# 04-AUDIO_TEST.net
KiCad netlist of a schematic drawn in Altium Designer
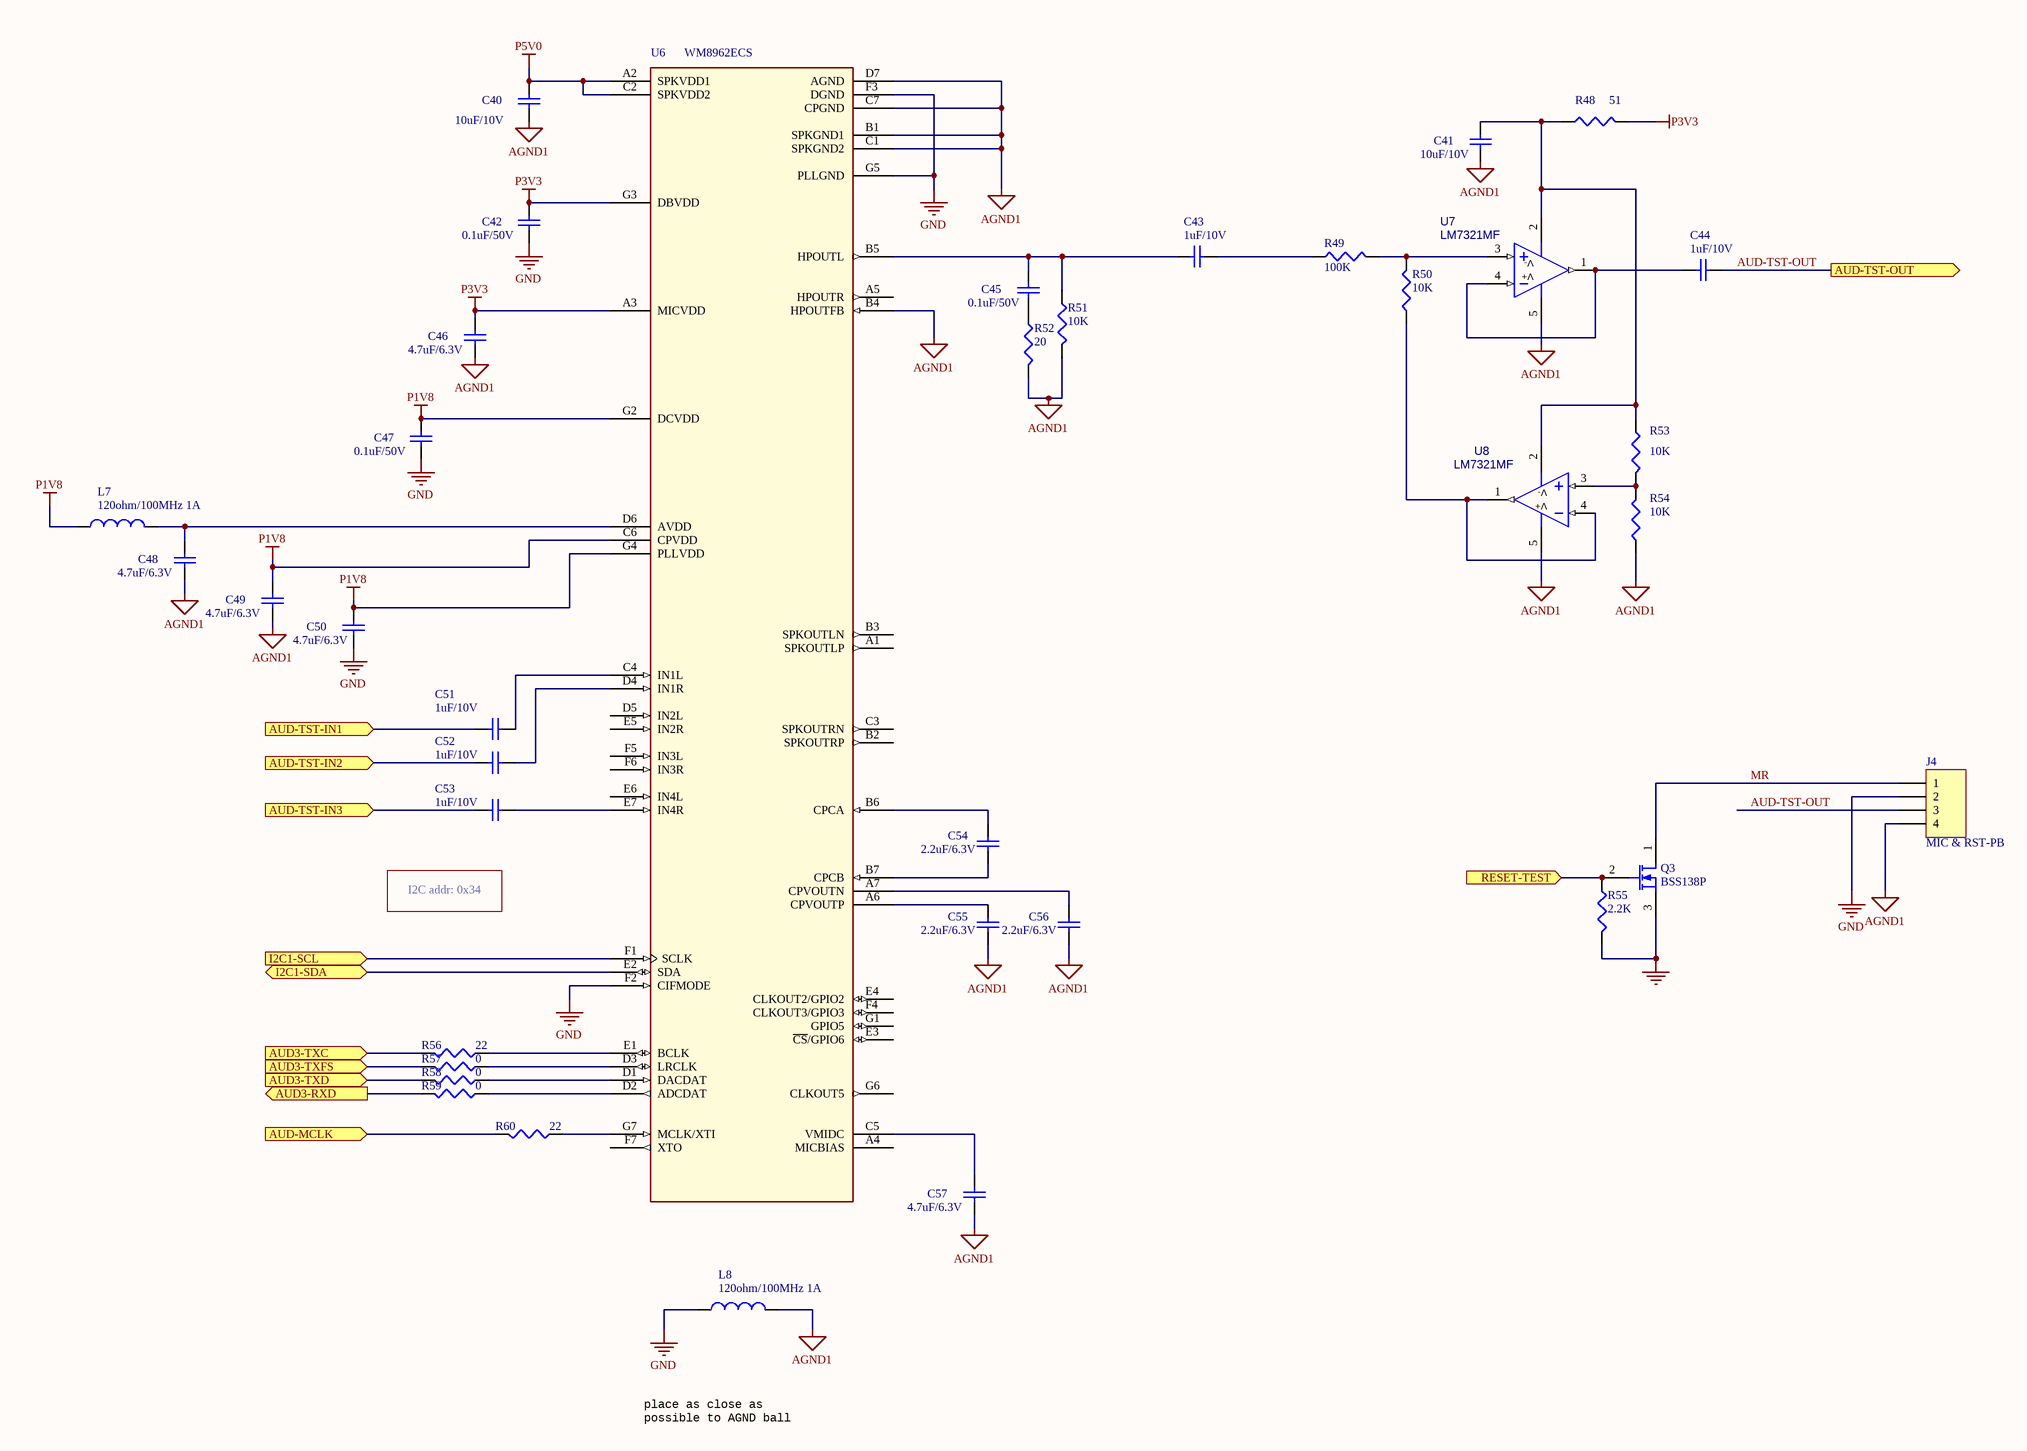
[diagram p0: 04-AUDIO_TEST.SchDoc]

(export (version "E")
  (design (tool "Eeschema 10.0.6"))
  (components
    (comp (ref "C40")
      (value "10uF/10V")
      (footprint "0805")
      (description "Capacitor")
      (fields (field (name "PUBLISHER") "Altium Limited"))
      (libsource (lib "Miscellaneous Devices") (part "Cap"))
    )
    (comp (ref "C41")
      (value "10uF/10V")
      (footprint "0805")
      (description "Capacitor")
      (fields (field (name "PUBLISHER") "Altium Limited"))
      (libsource (lib "Miscellaneous Devices") (part "Cap"))
    )
    (comp (ref "C42")
      (value "0.1uF/50V")
      (footprint "0402")
      (description "Capacitor")
      (fields (field (name "PUBLISHER") "Altium Limited"))
      (libsource (lib "Miscellaneous Devices") (part "Cap"))
    )
    (comp (ref "C43")
      (value "1uF/10V")
      (footprint "0402")
      (description "Capacitor")
      (fields (field (name "PUBLISHER") "Altium Limited"))
      (libsource (lib "Miscellaneous Devices") (part "Cap"))
    )
    (comp (ref "C44")
      (value "1uF/10V")
      (footprint "0402")
      (description "Capacitor")
      (fields (field (name "PUBLISHER") "Altium Limited"))
      (libsource (lib "Miscellaneous Devices") (part "Cap"))
    )
    (comp (ref "C45")
      (value "0.1uF/50V")
      (footprint "0402")
      (description "Capacitor")
      (fields (field (name "PUBLISHER") "Altium Limited"))
      (libsource (lib "Miscellaneous Devices") (part "Cap"))
    )
    (comp (ref "C46")
      (value "4.7uF/6.3V")
      (footprint "0603")
      (description "Capacitor")
      (fields (field (name "PUBLISHER") "Altium Limited"))
      (libsource (lib "Miscellaneous Devices") (part "Cap"))
    )
    (comp (ref "C47")
      (value "0.1uF/50V")
      (footprint "0402")
      (description "Capacitor")
      (fields (field (name "PUBLISHER") "Altium Limited"))
      (libsource (lib "Miscellaneous Devices") (part "Cap"))
    )
    (comp (ref "C48")
      (value "4.7uF/6.3V")
      (footprint "0603")
      (description "Capacitor")
      (fields (field (name "PUBLISHER") "Altium Limited"))
      (libsource (lib "Miscellaneous Devices") (part "Cap"))
    )
    (comp (ref "C49")
      (value "4.7uF/6.3V")
      (footprint "0603")
      (description "Capacitor")
      (fields (field (name "PUBLISHER") "Altium Limited"))
      (libsource (lib "Miscellaneous Devices") (part "Cap"))
    )
    (comp (ref "C50")
      (value "4.7uF/6.3V")
      (footprint "0603")
      (description "Capacitor")
      (fields (field (name "PUBLISHER") "Altium Limited"))
      (libsource (lib "Miscellaneous Devices") (part "Cap"))
    )
    (comp (ref "C51")
      (value "1uF/10V")
      (footprint "0402")
      (description "Capacitor")
      (fields (field (name "PUBLISHER") "Altium Limited"))
      (libsource (lib "Miscellaneous Devices") (part "Cap"))
    )
    (comp (ref "C52")
      (value "1uF/10V")
      (footprint "0402")
      (description "Capacitor")
      (fields (field (name "PUBLISHER") "Altium Limited"))
      (libsource (lib "Miscellaneous Devices") (part "Cap"))
    )
    (comp (ref "C53")
      (value "1uF/10V")
      (footprint "0402")
      (description "Capacitor")
      (fields (field (name "PUBLISHER") "Altium Limited"))
      (libsource (lib "Miscellaneous Devices") (part "Cap"))
    )
    (comp (ref "C54")
      (value "2.2uF/6.3V")
      (footprint "0402")
      (description "Capacitor")
      (fields (field (name "PUBLISHER") "Altium Limited"))
      (libsource (lib "Miscellaneous Devices") (part "Cap"))
    )
    (comp (ref "C55")
      (value "2.2uF/6.3V")
      (footprint "0402")
      (description "Capacitor")
      (fields (field (name "PUBLISHER") "Altium Limited"))
      (libsource (lib "Miscellaneous Devices") (part "Cap"))
    )
    (comp (ref "C56")
      (value "2.2uF/6.3V")
      (footprint "0402")
      (description "Capacitor")
      (fields (field (name "PUBLISHER") "Altium Limited"))
      (libsource (lib "Miscellaneous Devices") (part "Cap"))
    )
    (comp (ref "C57")
      (value "4.7uF/6.3V")
      (footprint "0603")
      (description "Capacitor")
      (fields (field (name "PUBLISHER") "Altium Limited"))
      (libsource (lib "Miscellaneous Devices") (part "Cap"))
    )
    (comp (ref "J4")
      (value "MIC & RST-PB")
      (footprint "FPC1.0-DR-SMD-4P-F2.0")
      (description "Header, 4-Pin")
      (fields (field (name "PUBLISHER") "Altium Limited"))
      (libsource (lib "Miscellaneous Connectors") (part "Header 4"))
    )
    (comp (ref "L7")
      (value "120ohm/100MHz 1A")
      (footprint "0603")
      (description "Inductor")
      (fields (field (name "PUBLISHER") "Altium Limited"))
      (libsource (lib "Miscellaneous Devices") (part "Inductor"))
    )
    (comp (ref "L8")
      (value "120ohm/100MHz 1A")
      (footprint "0603")
      (description "Inductor")
      (fields (field (name "PUBLISHER") "Altium Limited"))
      (libsource (lib "Miscellaneous Devices") (part "Inductor"))
    )
    (comp (ref "Q3")
      (value "BSS138P")
      (footprint "NPN")
      (description "N-Channel MOSFET")
      (fields (field (name "PUBLISHER") "Altium Limited"))
      (libsource (lib "Miscellaneous Devices") (part "MOSFET-N"))
    )
    (comp (ref "R48") (value "51") (footprint "0402") (libsource (lib "*") (part "CR16-1003FM")))
    (comp (ref "R49") (value "100K") (footprint "0402") (libsource (lib "*") (part "CR16-1003FM")))
    (comp (ref "R50") (value "10K") (footprint "0402") (libsource (lib "*") (part "CR16-1003FM")))
    (comp (ref "R51") (value "10K") (footprint "0402") (libsource (lib "*") (part "CR16-1003FM")))
    (comp (ref "R52") (value "20") (footprint "0402") (libsource (lib "*") (part "CR16-1003FM")))
    (comp (ref "R53") (value "10K") (footprint "0402") (libsource (lib "*") (part "CR16-1003FM")))
    (comp (ref "R54") (value "10K") (footprint "0402") (libsource (lib "*") (part "CR16-1003FM")))
    (comp (ref "R55")
      (value "2.2K")
      (footprint "0402")
      (description "Resistor")
      (fields (field (name "PUBLISHER") "Altium Limited"))
      (libsource (lib "Miscellaneous Devices") (part "Res3"))
    )
    (comp (ref "R56") (value "22") (footprint "0402") (libsource (lib "*") (part "CR16-1003FM")))
    (comp (ref "R57") (value "0") (footprint "0402") (libsource (lib "*") (part "CR16-1003FM")))
    (comp (ref "R58") (value "0") (footprint "0402") (libsource (lib "*") (part "CR16-1003FM")))
    (comp (ref "R59") (value "0") (footprint "0402") (libsource (lib "*") (part "CR16-1003FM")))
    (comp (ref "R60") (value "22") (footprint "0402") (libsource (lib "*") (part "CR16-1003FM")))
    (comp (ref "U6")
      (value "WM8962ECS")
      (footprint "BGA49")
      (description "IC AUDIO CODEC 24BIT DAC 2 CH ADC 1.8V BGA49")
      (libsource (lib "*") (part "WM8962_BGA_49P_CUST"))
    )
    (comp (ref "U7")
      (value "LM7321MF")
      (footprint "SOT23-5")
      (description "Single 30V High Output Current and Unlimited Capacitive Load Op Amp")
      (fields
        (field (name "MANUFACTURER") "National Semiconductor")
        (field (name "PUBLISHER") "National Semiconductor")
      )
      (libsource (lib "NSC Amplifier") (part "LM7321MF"))
    )
    (comp (ref "U8")
      (value "LM7321MF")
      (footprint "SOT23-5")
      (description "Single 30V High Output Current and Unlimited Capacitive Load Op Amp")
      (fields
        (field (name "MANUFACTURER") "National Semiconductor")
        (field (name "PUBLISHER") "National Semiconductor")
      )
      (libsource (lib "NSC Amplifier") (part "LM7321MF"))
    )
  )
  (nets
    (net (code "1") (name "/AUD-MCLK") (class "Default")
      (node (ref "R60") (pin "2") (pinfunction "2_2") (pintype "passive"))
    )
    (net (code "2") (name "/AUD-TST-IN1") (class "Default")
      (node (ref "C51") (pin "2") (pinfunction "2_2") (pintype "passive"))
    )
    (net (code "3") (name "/AUD-TST-IN2") (class "Default")
      (node (ref "C52") (pin "2") (pinfunction "2_2") (pintype "passive"))
    )
    (net (code "4") (name "/AUD-TST-IN3") (class "Default")
      (node (ref "C53") (pin "2") (pinfunction "2_2") (pintype "passive"))
    )
    (net (code "5") (name "/AUD-TST-OUT") (class "Default")
      (node (ref "C44") (pin "1") (pinfunction "1_1") (pintype "passive"))
      (node (ref "J4") (pin "3") (pinfunction "3_3") (pintype "passive"))
    )
    (net (code "6") (name "/AUD3-RXD") (class "Default")
      (node (ref "R59") (pin "2") (pinfunction "2_2") (pintype "passive"))
    )
    (net (code "7") (name "/AUD3-TXC") (class "Default")
      (node (ref "R56") (pin "2") (pinfunction "2_2") (pintype "passive"))
    )
    (net (code "8") (name "/AUD3-TXD") (class "Default")
      (node (ref "R58") (pin "2") (pinfunction "2_2") (pintype "passive"))
    )
    (net (code "9") (name "/AUD3-TXFS") (class "Default")
      (node (ref "R57") (pin "2") (pinfunction "2_2") (pintype "passive"))
    )
    (net (code "10") (name "/I2C1-SCL") (class "Default")
      (node (ref "U6") (pin "F1") (pinfunction "SCLK_F1") (pintype "input"))
    )
    (net (code "11") (name "/I2C1-SDA") (class "Default")
      (node (ref "U6") (pin "E2") (pinfunction "SDA_E2") (pintype "bidirectional"))
    )
    (net (code "12") (name "/MR") (class "Default")
      (node (ref "J4") (pin "1") (pinfunction "1_1") (pintype "passive"))
      (node (ref "Q3") (pin "1") (pinfunction "D_1") (pintype "passive"))
    )
    (net (code "13") (name "/RESET-TEST") (class "Default")
      (node (ref "Q3") (pin "2") (pinfunction "G_2") (pintype "passive"))
      (node (ref "R55") (pin "1") (pinfunction "1_1") (pintype "passive"))
    )
    (net (code "14") (name "AGND1") (class "Default")
      (node (ref "C40") (pin "1") (pinfunction "1_1") (pintype "passive"))
      (node (ref "C41") (pin "2") (pinfunction "2_2") (pintype "passive"))
      (node (ref "C46") (pin "1") (pinfunction "1_1") (pintype "passive"))
      (node (ref "C48") (pin "1") (pinfunction "1_1") (pintype "passive"))
      (node (ref "C49") (pin "1") (pinfunction "1_1") (pintype "passive"))
      (node (ref "C55") (pin "1") (pinfunction "1_1") (pintype "passive"))
      (node (ref "C56") (pin "1") (pinfunction "1_1") (pintype "passive"))
      (node (ref "C57") (pin "1") (pinfunction "1_1") (pintype "passive"))
      (node (ref "J4") (pin "4") (pinfunction "4_4") (pintype "passive"))
      (node (ref "L8") (pin "2") (pinfunction "2_2") (pintype "passive"))
      (node (ref "R51") (pin "2") (pinfunction "2_2") (pintype "passive"))
      (node (ref "R52") (pin "2") (pinfunction "2_2") (pintype "passive"))
      (node (ref "R54") (pin "1") (pinfunction "1_1") (pintype "passive"))
      (node (ref "U6") (pin "B1") (pinfunction "SPKGND1_B1") (pintype "power_in"))
      (node (ref "U6") (pin "B4") (pinfunction "HPOUTFB_B4") (pintype "input"))
      (node (ref "U6") (pin "C1") (pinfunction "SPKGND2_C1") (pintype "power_in"))
      (node (ref "U6") (pin "C7") (pinfunction "CPGND_C7") (pintype "power_in"))
      (node (ref "U6") (pin "D7") (pinfunction "AGND_D7") (pintype "power_in"))
      (node (ref "U7") (pin "5") (pinfunction "V+_5") (pintype "power_in"))
      (node (ref "U8") (pin "5") (pinfunction "V+_5") (pintype "power_in"))
    )
    (net (code "15") (name "GND") (class "Default")
      (node (ref "C42") (pin "1") (pinfunction "1_1") (pintype "passive"))
      (node (ref "C47") (pin "1") (pinfunction "1_1") (pintype "passive"))
      (node (ref "C50") (pin "1") (pinfunction "1_1") (pintype "passive"))
      (node (ref "J4") (pin "2") (pinfunction "2_2") (pintype "passive"))
      (node (ref "L8") (pin "1") (pinfunction "1_1") (pintype "passive"))
      (node (ref "Q3") (pin "3") (pinfunction "S_3") (pintype "passive"))
      (node (ref "R55") (pin "2") (pinfunction "2_2") (pintype "passive"))
      (node (ref "U6") (pin "F2") (pinfunction "CIFMODE_F2") (pintype "input"))
      (node (ref "U6") (pin "F3") (pinfunction "DGND_F3") (pintype "power_in"))
      (node (ref "U6") (pin "G5") (pinfunction "PLLGND_G5") (pintype "power_in"))
    )
    (net (code "16") (name "Net-(C43-Pad1)") (class "Default")
      (node (ref "C43") (pin "1") (pinfunction "1_1") (pintype "passive"))
      (node (ref "R49") (pin "1") (pinfunction "1_1") (pintype "passive"))
    )
    (net (code "17") (name "Net-(C45-Pad1)") (class "Default")
      (node (ref "C45") (pin "1") (pinfunction "1_1") (pintype "passive"))
      (node (ref "R52") (pin "1") (pinfunction "1_1") (pintype "passive"))
    )
    (net (code "18") (name "Net-(U6-ADCDAT)") (class "Default")
      (node (ref "R59") (pin "1") (pinfunction "1_1") (pintype "passive"))
      (node (ref "U6") (pin "D2") (pinfunction "ADCDAT_D2") (pintype "output"))
    )
    (net (code "19") (name "Net-(U6-AVDD)") (class "Default")
      (node (ref "C48") (pin "2") (pinfunction "2_2") (pintype "passive"))
      (node (ref "L7") (pin "2") (pinfunction "2_2") (pintype "passive"))
      (node (ref "U6") (pin "D6") (pinfunction "AVDD_D6") (pintype "power_in"))
    )
    (net (code "20") (name "Net-(U6-BCLK)") (class "Default")
      (node (ref "R56") (pin "1") (pinfunction "1_1") (pintype "passive"))
      (node (ref "U6") (pin "E1") (pinfunction "BCLK_E1") (pintype "bidirectional"))
    )
    (net (code "21") (name "Net-(U6-CPCA)") (class "Default")
      (node (ref "C54") (pin "2") (pinfunction "2_2") (pintype "passive"))
      (node (ref "U6") (pin "B6") (pinfunction "CPCA_B6") (pintype "input"))
    )
    (net (code "22") (name "Net-(U6-CPCB)") (class "Default")
      (node (ref "C54") (pin "1") (pinfunction "1_1") (pintype "passive"))
      (node (ref "U6") (pin "B7") (pinfunction "CPCB_B7") (pintype "input"))
    )
    (net (code "23") (name "Net-(U6-CPVOUTN)") (class "Default")
      (node (ref "C56") (pin "2") (pinfunction "2_2") (pintype "passive"))
      (node (ref "U6") (pin "A7") (pinfunction "CPVOUTN_A7") (pintype "power_in"))
    )
    (net (code "24") (name "Net-(U6-CPVOUTP)") (class "Default")
      (node (ref "C55") (pin "2") (pinfunction "2_2") (pintype "passive"))
      (node (ref "U6") (pin "A6") (pinfunction "CPVOUTP_A6") (pintype "power_in"))
    )
    (net (code "25") (name "Net-(U6-DACDAT)") (class "Default")
      (node (ref "R58") (pin "1") (pinfunction "1_1") (pintype "passive"))
      (node (ref "U6") (pin "D1") (pinfunction "DACDAT_D1") (pintype "input"))
    )
    (net (code "26") (name "Net-(U6-HPOUTL)") (class "Default")
      (node (ref "C43") (pin "2") (pinfunction "2_2") (pintype "passive"))
      (node (ref "C45") (pin "2") (pinfunction "2_2") (pintype "passive"))
      (node (ref "R51") (pin "1") (pinfunction "1_1") (pintype "passive"))
      (node (ref "U6") (pin "B5") (pinfunction "HPOUTL_B5") (pintype "output"))
    )
    (net (code "27") (name "Net-(U6-IN1L)") (class "Default")
      (node (ref "C51") (pin "1") (pinfunction "1_1") (pintype "passive"))
      (node (ref "U6") (pin "C4") (pinfunction "IN1L_C4") (pintype "input"))
    )
    (net (code "28") (name "Net-(U6-IN1R)") (class "Default")
      (node (ref "C52") (pin "1") (pinfunction "1_1") (pintype "passive"))
      (node (ref "U6") (pin "D4") (pinfunction "IN1R_D4") (pintype "input"))
    )
    (net (code "29") (name "Net-(U6-IN4R)") (class "Default")
      (node (ref "C53") (pin "1") (pinfunction "1_1") (pintype "passive"))
      (node (ref "U6") (pin "E7") (pinfunction "IN4R_E7") (pintype "input"))
    )
    (net (code "30") (name "Net-(U6-LRCLK)") (class "Default")
      (node (ref "R57") (pin "1") (pinfunction "1_1") (pintype "passive"))
      (node (ref "U6") (pin "D3") (pinfunction "LRCLK_D3") (pintype "bidirectional"))
    )
    (net (code "31") (name "Net-(U6-MCLK{slash}XTI)") (class "Default")
      (node (ref "R60") (pin "1") (pinfunction "1_1") (pintype "passive"))
      (node (ref "U6") (pin "G7") (pinfunction "MCLK/XTI_G7") (pintype "input"))
    )
    (net (code "32") (name "Net-(U6-VMIDC)") (class "Default")
      (node (ref "C57") (pin "2") (pinfunction "2_2") (pintype "passive"))
      (node (ref "U6") (pin "C5") (pinfunction "VMIDC_C5") (pintype "power_in"))
    )
    (net (code "33") (name "Net-(U7-IN+)") (class "Default")
      (node (ref "R49") (pin "2") (pinfunction "2_2") (pintype "passive"))
      (node (ref "R50") (pin "2") (pinfunction "2_2") (pintype "passive"))
      (node (ref "U7") (pin "3") (pinfunction "IN+_3") (pintype "input"))
    )
    (net (code "34") (name "Net-(U7-IN-)") (class "Default")
      (node (ref "C44") (pin "2") (pinfunction "2_2") (pintype "passive"))
      (node (ref "U7") (pin "1") (pinfunction "OUT_1") (pintype "output"))
      (node (ref "U7") (pin "4") (pinfunction "IN-_4") (pintype "input"))
    )
    (net (code "35") (name "Net-(U7-V-)") (class "Default")
      (node (ref "C41") (pin "1") (pinfunction "1_1") (pintype "passive"))
      (node (ref "R48") (pin "1") (pinfunction "1_1") (pintype "passive"))
      (node (ref "R53") (pin "1") (pinfunction "1_1") (pintype "passive"))
      (node (ref "U7") (pin "2") (pinfunction "V-_2") (pintype "power_in"))
      (node (ref "U8") (pin "2") (pinfunction "V-_2") (pintype "power_in"))
    )
    (net (code "36") (name "Net-(U8-IN+)") (class "Default")
      (node (ref "R53") (pin "2") (pinfunction "2_2") (pintype "passive"))
      (node (ref "R54") (pin "2") (pinfunction "2_2") (pintype "passive"))
      (node (ref "U8") (pin "3") (pinfunction "IN+_3") (pintype "input"))
    )
    (net (code "37") (name "Net-(U8-IN-)") (class "Default")
      (node (ref "R50") (pin "1") (pinfunction "1_1") (pintype "passive"))
      (node (ref "U8") (pin "1") (pinfunction "OUT_1") (pintype "output"))
      (node (ref "U8") (pin "4") (pinfunction "IN-_4") (pintype "input"))
    )
    (net (code "38") (name "P1V8") (class "Default")
      (node (ref "C47") (pin "2") (pinfunction "2_2") (pintype "passive"))
      (node (ref "C49") (pin "2") (pinfunction "2_2") (pintype "passive"))
      (node (ref "C50") (pin "2") (pinfunction "2_2") (pintype "passive"))
      (node (ref "L7") (pin "1") (pinfunction "1_1") (pintype "passive"))
      (node (ref "U6") (pin "C6") (pinfunction "CPVDD_C6") (pintype "power_in"))
      (node (ref "U6") (pin "G2") (pinfunction "DCVDD_G2") (pintype "power_in"))
      (node (ref "U6") (pin "G4") (pinfunction "PLLVDD_G4") (pintype "power_in"))
    )
    (net (code "39") (name "P3V3") (class "Default")
      (node (ref "C42") (pin "2") (pinfunction "2_2") (pintype "passive"))
      (node (ref "C46") (pin "2") (pinfunction "2_2") (pintype "passive"))
      (node (ref "R48") (pin "2") (pinfunction "2_2") (pintype "passive"))
      (node (ref "U6") (pin "A3") (pinfunction "MICVDD_A3") (pintype "power_in"))
      (node (ref "U6") (pin "G3") (pinfunction "DBVDD_G3") (pintype "power_in"))
    )
    (net (code "40") (name "P5V0") (class "Default")
      (node (ref "C40") (pin "2") (pinfunction "2_2") (pintype "passive"))
      (node (ref "U6") (pin "A2") (pinfunction "SPKVDD1_A2") (pintype "power_in"))
      (node (ref "U6") (pin "C2") (pinfunction "SPKVDD2_C2") (pintype "power_in"))
    )
    (net (code "41") (name "unconnected-(U6-CLKOUT2{slash}GPIO2-PadE4)") (class "Default")
      (node (ref "U6") (pin "E4") (pinfunction "CLKOUT2/GPIO2_E4") (pintype "bidirectional"))
    )
    (net (code "42") (name "unconnected-(U6-CLKOUT3{slash}GPIO3-PadF4)") (class "Default")
      (node (ref "U6") (pin "F4") (pinfunction "CLKOUT3/GPIO3_F4") (pintype "bidirectional"))
    )
    (net (code "43") (name "unconnected-(U6-CLKOUT5-PadG6)") (class "Default")
      (node (ref "U6") (pin "G6") (pinfunction "CLKOUT5_G6") (pintype "output"))
    )
    (net (code "44") (name "unconnected-(U6-GPIO5-PadG1)") (class "Default")
      (node (ref "U6") (pin "G1") (pinfunction "GPIO5_G1") (pintype "bidirectional"))
    )
    (net (code "45") (name "unconnected-(U6-HPOUTR-PadA5)") (class "Default")
      (node (ref "U6") (pin "A5") (pinfunction "HPOUTR_A5") (pintype "output"))
    )
    (net (code "46") (name "unconnected-(U6-IN2L-PadD5)") (class "Default")
      (node (ref "U6") (pin "D5") (pinfunction "IN2L_D5") (pintype "input"))
    )
    (net (code "47") (name "unconnected-(U6-IN2R-PadE5)") (class "Default")
      (node (ref "U6") (pin "E5") (pinfunction "IN2R_E5") (pintype "input"))
    )
    (net (code "48") (name "unconnected-(U6-IN3L-PadF5)") (class "Default")
      (node (ref "U6") (pin "F5") (pinfunction "IN3L_F5") (pintype "input"))
    )
    (net (code "49") (name "unconnected-(U6-IN3R-PadF6)") (class "Default")
      (node (ref "U6") (pin "F6") (pinfunction "IN3R_F6") (pintype "input"))
    )
    (net (code "50") (name "unconnected-(U6-IN4L-PadE6)") (class "Default")
      (node (ref "U6") (pin "E6") (pinfunction "IN4L_E6") (pintype "input"))
    )
    (net (code "51") (name "unconnected-(U6-MICBIAS-PadA4)") (class "Default")
      (node (ref "U6") (pin "A4") (pinfunction "MICBIAS_A4") (pintype "passive"))
    )
    (net (code "52") (name "unconnected-(U6-SPKOUTLN-PadB3)") (class "Default")
      (node (ref "U6") (pin "B3") (pinfunction "SPKOUTLN_B3") (pintype "output"))
    )
    (net (code "53") (name "unconnected-(U6-SPKOUTLP-PadA1)") (class "Default")
      (node (ref "U6") (pin "A1") (pinfunction "SPKOUTLP_A1") (pintype "output"))
    )
    (net (code "54") (name "unconnected-(U6-SPKOUTRN-PadC3)") (class "Default")
      (node (ref "U6") (pin "C3") (pinfunction "SPKOUTRN_C3") (pintype "output"))
    )
    (net (code "55") (name "unconnected-(U6-SPKOUTRP-PadB2)") (class "Default")
      (node (ref "U6") (pin "B2") (pinfunction "SPKOUTRP_B2") (pintype "output"))
    )
    (net (code "56") (name "unconnected-(U6-XTO-PadF7)") (class "Default")
      (node (ref "U6") (pin "F7") (pinfunction "XTO_F7") (pintype "output"))
    )
    (net (code "57") (name "unconnected-(U6-~{CS}{slash}GPIO6-PadE3)") (class "Default")
      (node (ref "U6") (pin "E3") (pinfunction "~{CS}/GPIO6_E3") (pintype "bidirectional"))
    )
  )
)
